# triacTriggerCpuBoard.net
KiCad netlist of a schematic drawn in EAGLE
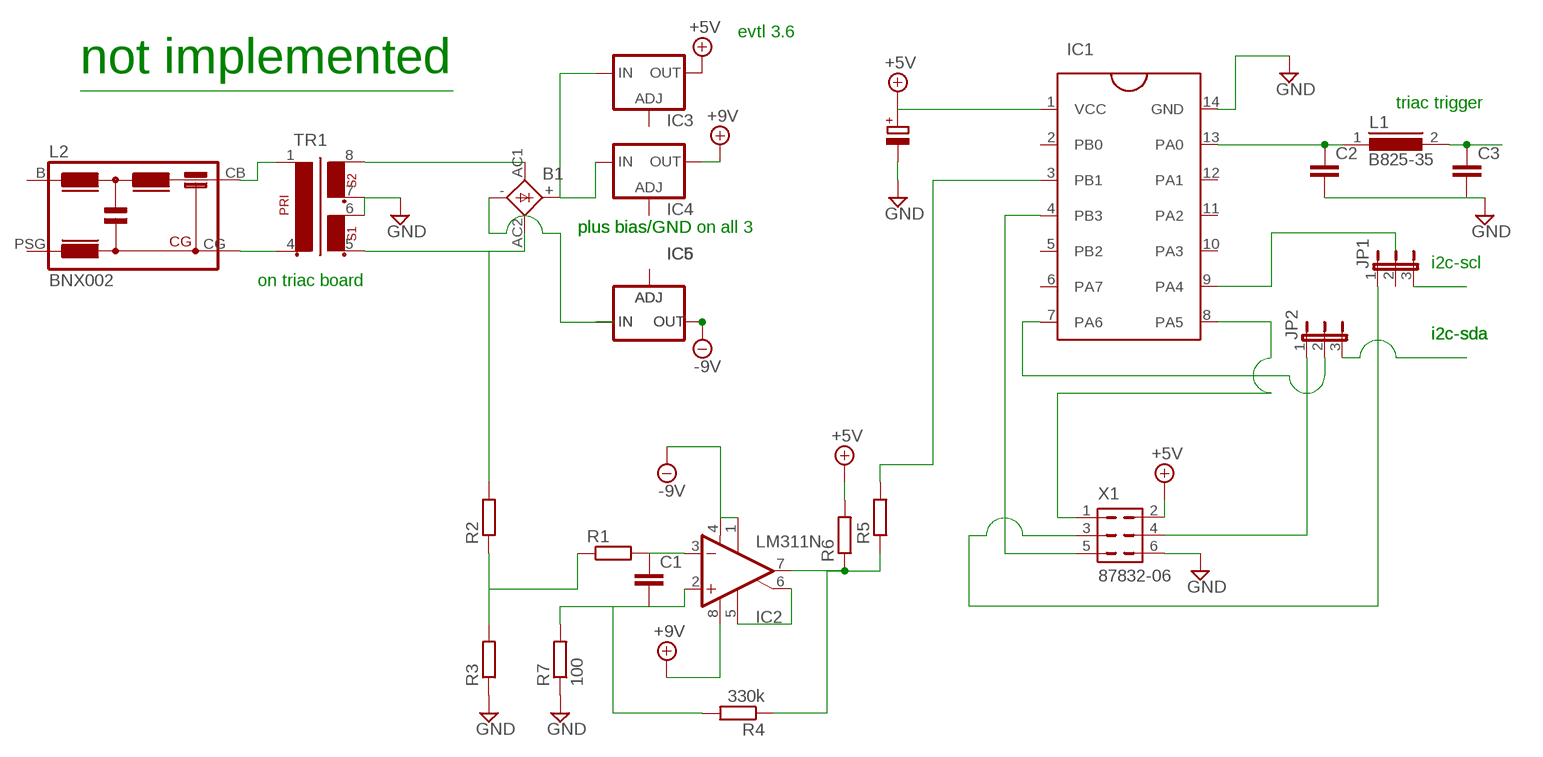
[diagram p0: schematic, sheet 1]

(export (version "E")
  (design (tool "Eeschema 10.0.6"))
  (components
    (comp (ref "B1")
      (value "2KBB-R")
      (footprint "eagle-import:2KBB-R")
      (libsource (lib "eagle-import") (part "2KBB-R"))
    )
    (comp (ref "C1")
      (value "C2,5-3")
      (footprint "eagle-import:C2.5-3")
      (libsource (lib "eagle-import") (part "C2,5-3"))
    )
    (comp (ref "C2")
      (value "C2,5-3")
      (footprint "eagle-import:C2.5-3")
      (libsource (lib "eagle-import") (part "C2,5-3"))
    )
    (comp (ref "C3")
      (value "C2,5-3")
      (footprint "eagle-import:C2.5-3")
      (libsource (lib "eagle-import") (part "C2,5-3"))
    )
    (comp (ref "IC1")
      (value "ATTINY4414P3")
      (footprint "eagle-import:DIL14")
      (libsource (lib "eagle-import") (part "ATTINY4414P3"))
    )
    (comp (ref "IC2")
      (value "LM311N")
      (footprint "eagle-import:DIL08")
      (libsource (lib "eagle-import") (part "LM311N"))
    )
    (comp (ref "IC3")
      (value "LM317-TO3")
      (footprint "eagle-import:TO3-K02")
      (libsource (lib "eagle-import") (part "LM317-TO3"))
    )
    (comp (ref "IC4")
      (value "LM317-TO3")
      (footprint "eagle-import:TO3-K02")
      (libsource (lib "eagle-import") (part "LM317-TO3"))
    )
    (comp (ref "IC5")
      (value "LM337TS")
      (footprint "eagle-import:337TS")
      (libsource (lib "eagle-import") (part "LM337TS"))
    )
    (comp (ref "IC6")
      (value "LM337TS")
      (footprint "eagle-import:337TS")
      (libsource (lib "eagle-import") (part "LM337TS"))
    )
    (comp (ref "JP1")
      (value "JP2E")
      (footprint "eagle-import:JP2")
      (libsource (lib "eagle-import") (part "JP2E"))
    )
    (comp (ref "JP2")
      (value "JP2E")
      (footprint "eagle-import:JP2")
      (libsource (lib "eagle-import") (part "JP2E"))
    )
    (comp (ref "L1")
      (value "B825-35")
      (footprint "eagle-import:B825-35")
      (libsource (lib "eagle-import") (part "B825-35"))
    )
    (comp (ref "L2")
      (value "BNX002")
      (footprint "eagle-import:BNX002")
      (libsource (lib "eagle-import") (part "BNX002"))
    )
    (comp (ref "R1")
      (value "R-EU_0207/10")
      (footprint "eagle-import:0207_10")
      (libsource (lib "eagle-import") (part "R-EU_0207/10"))
    )
    (comp (ref "R2")
      (value "R-EU_0207/10")
      (footprint "eagle-import:0207_10")
      (libsource (lib "eagle-import") (part "R-EU_0207/10"))
    )
    (comp (ref "R3")
      (value "R-EU_0207/10")
      (footprint "eagle-import:0207_10")
      (libsource (lib "eagle-import") (part "R-EU_0207/10"))
    )
    (comp (ref "R4")
      (value "330k")
      (footprint "eagle-import:0207_10")
      (libsource (lib "eagle-import") (part "R-EU_0207/10"))
    )
    (comp (ref "R5")
      (value "R-EU_0207/10")
      (footprint "eagle-import:0207_10")
      (libsource (lib "eagle-import") (part "R-EU_0207/10"))
    )
    (comp (ref "R6")
      (value "R-EU_0207/10")
      (footprint "eagle-import:0207_10")
      (libsource (lib "eagle-import") (part "R-EU_0207/10"))
    )
    (comp (ref "R7")
      (value "100")
      (footprint "eagle-import:0207_10")
      (libsource (lib "eagle-import") (part "R-EU_0207/10"))
    )
    (comp (ref "TR1")
      (value "EE20-2")
      (footprint "eagle-import:EE20-2")
      (libsource (lib "eagle-import") (part "EE20-2"))
    )
    (comp (ref "X1")
      (value "87832-06")
      (footprint "eagle-import:87832-06")
      (libsource (lib "eagle-import") (part "87832-06"))
    )
  )
  (nets
    (net (code "1") (name "+5V") (class "Default")
      (node (ref "IC1") (pin "1") (pinfunction "VCC_1") (pintype "power_in"))
      (node (ref "IC3") (pin "3") (pinfunction "OUT_3") (pintype "passive"))
      (node (ref "R6") (pin "2") (pinfunction "2_2") (pintype "passive"))
      (node (ref "X1") (pin "2") (pinfunction "2_2") (pintype "passive"))
    )
    (net (code "2") (name "+9V") (class "Default")
      (node (ref "IC2") (pin "8") (pinfunction "V+_8") (pintype "power_in"))
      (node (ref "IC4") (pin "3") (pinfunction "OUT_3") (pintype "passive"))
    )
    (net (code "3") (name "-9V") (class "Default")
      (node (ref "IC2") (pin "1") (pinfunction "GND_1") (pintype "passive"))
      (node (ref "IC2") (pin "4") (pinfunction "V-_4") (pintype "power_in"))
      (node (ref "IC5") (pin "3") (pinfunction "OUT_3") (pintype "passive"))
      (node (ref "IC6") (pin "3") (pinfunction "OUT_3") (pintype "passive"))
    )
    (net (code "4") (name "GND") (class "Default")
      (node (ref "C2") (pin "2") (pinfunction "2_2") (pintype "passive"))
      (node (ref "IC1") (pin "14") (pinfunction "GND_14") (pintype "power_in"))
      (node (ref "R3") (pin "1") (pinfunction "1_1") (pintype "passive"))
      (node (ref "R7") (pin "1") (pinfunction "1_1") (pintype "passive"))
      (node (ref "TR1") (pin "6") (pinfunction "4_6") (pintype "passive"))
      (node (ref "TR1") (pin "7") (pinfunction "5_7") (pintype "passive"))
      (node (ref "X1") (pin "6") (pinfunction "6_6") (pintype "passive"))
    )
    (net (code "5") (name "Net-(C3-Pad1)") (class "Default")
      (node (ref "C3") (pin "1") (pinfunction "1_1") (pintype "passive"))
      (node (ref "L1") (pin "2") (pinfunction "2_2") (pintype "passive"))
    )
    (net (code "6") (name "Net-(IC1-PA0)") (class "Default")
      (node (ref "C2") (pin "1") (pinfunction "1_1") (pintype "passive"))
      (node (ref "IC1") (pin "13") (pinfunction "PA0_13") (pintype "bidirectional"))
      (node (ref "L1") (pin "1") (pinfunction "1_1") (pintype "passive"))
    )
    (net (code "7") (name "Net-(IC1-PA5)") (class "Default")
      (node (ref "IC1") (pin "8") (pinfunction "PA5_8") (pintype "bidirectional"))
      (node (ref "X1") (pin "1") (pinfunction "1_1") (pintype "passive"))
    )
    (net (code "8") (name "Net-(IC1-PA6)") (class "Default")
      (node (ref "IC1") (pin "7") (pinfunction "PA6_7") (pintype "bidirectional"))
      (node (ref "JP2") (pin "2") (pinfunction "2_2") (pintype "passive"))
    )
    (net (code "9") (name "Net-(IC1-PB1)") (class "Default")
      (node (ref "IC1") (pin "3") (pinfunction "PB1_3") (pintype "bidirectional"))
      (node (ref "R5") (pin "2") (pinfunction "2_2") (pintype "passive"))
    )
    (net (code "10") (name "Net-(IC1-PB3)") (class "Default")
      (node (ref "IC1") (pin "4") (pinfunction "PB3_4") (pintype "bidirectional"))
      (node (ref "X1") (pin "5") (pinfunction "5_5") (pintype "passive"))
    )
    (net (code "11") (name "Net-(IC2-+IN)") (class "Default")
      (node (ref "C1") (pin "2") (pinfunction "2_2") (pintype "passive"))
      (node (ref "IC2") (pin "2") (pinfunction "+IN_2") (pintype "input"))
      (node (ref "R4") (pin "2") (pinfunction "2_2") (pintype "passive"))
      (node (ref "R7") (pin "2") (pinfunction "2_2") (pintype "passive"))
    )
    (net (code "12") (name "Net-(IC2--IN)") (class "Default")
      (node (ref "C1") (pin "1") (pinfunction "1_1") (pintype "passive"))
      (node (ref "IC2") (pin "3") (pinfunction "-IN_3") (pintype "input"))
      (node (ref "R1") (pin "2") (pinfunction "2_2") (pintype "passive"))
    )
    (net (code "13") (name "Net-(IC2-ON)") (class "Default")
      (node (ref "IC2") (pin "5") (pinfunction "ON_5") (pintype "passive"))
      (node (ref "IC2") (pin "6") (pinfunction "ON/STR_6") (pintype "passive"))
    )
    (net (code "14") (name "Net-(IC2-OUT)") (class "Default")
      (node (ref "IC2") (pin "7") (pinfunction "OUT_7") (pintype "output"))
      (node (ref "R4") (pin "1") (pinfunction "1_1") (pintype "passive"))
      (node (ref "R5") (pin "1") (pinfunction "1_1") (pintype "passive"))
      (node (ref "R6") (pin "1") (pinfunction "1_1") (pintype "passive"))
    )
    (net (code "15") (name "Net-(IC3-IN)") (class "Default")
      (node (ref "B1") (pin "+") (pinfunction "+_+") (pintype "passive"))
      (node (ref "IC3") (pin "1") (pinfunction "IN_1") (pintype "input"))
      (node (ref "IC4") (pin "1") (pinfunction "IN_1") (pintype "input"))
    )
    (net (code "16") (name "Net-(IC5-ADJ)") (class "Default")
      (node (ref "IC5") (pin "1") (pinfunction "ADJ_1") (pintype "input"))
      (node (ref "IC6") (pin "1") (pinfunction "ADJ_1") (pintype "input"))
    )
    (net (code "17") (name "Net-(IC5-IN)") (class "Default")
      (node (ref "B1") (pin "-") (pinfunction "-_-") (pintype "passive"))
      (node (ref "IC5") (pin "2") (pinfunction "IN_2") (pintype "input"))
      (node (ref "IC6") (pin "2") (pinfunction "IN_2") (pintype "input"))
    )
    (net (code "18") (name "Net-(JP1-Pad1)") (class "Default")
      (node (ref "JP1") (pin "1") (pinfunction "1_1") (pintype "passive"))
      (node (ref "X1") (pin "3") (pinfunction "3_3") (pintype "passive"))
    )
    (net (code "19") (name "Net-(JP2-Pad1)") (class "Default")
      (node (ref "JP2") (pin "1") (pinfunction "1_1") (pintype "passive"))
      (node (ref "X1") (pin "4") (pinfunction "4_4") (pintype "passive"))
    )
    (net (code "20") (name "Net-(L2-PadCB)") (class "Default")
      (node (ref "L2") (pin "CB") (pinfunction "CB_CB") (pintype "passive"))
      (node (ref "TR1") (pin "1") (pinfunction "1_1") (pintype "passive"))
    )
    (net (code "21") (name "Net-(R1-Pad1)") (class "Default")
      (node (ref "R1") (pin "1") (pinfunction "1_1") (pintype "passive"))
      (node (ref "R2") (pin "1") (pinfunction "1_1") (pintype "passive"))
      (node (ref "R3") (pin "2") (pinfunction "2_2") (pintype "passive"))
    )
    (net (code "22") (name "Net-(TR1-2)") (class "Default")
      (node (ref "L2") (pin "CG") (pinfunction "CG_CG") (pintype "passive"))
      (node (ref "TR1") (pin "4") (pinfunction "2_4") (pintype "passive"))
    )
    (net (code "23") (name "Net-(TR1-3)") (class "Default")
      (node (ref "B1") (pin "AC2") (pinfunction "AC2_AC2") (pintype "passive"))
      (node (ref "R2") (pin "2") (pinfunction "2_2") (pintype "passive"))
      (node (ref "TR1") (pin "5") (pinfunction "3_5") (pintype "passive"))
    )
    (net (code "24") (name "Net-(TR1-6)") (class "Default")
      (node (ref "B1") (pin "AC1") (pinfunction "AC1_AC1") (pintype "passive"))
      (node (ref "TR1") (pin "8") (pinfunction "6_8") (pintype "passive"))
    )
    (net (code "25") (name "unconnected-(C3-Pad2)") (class "Default")
      (node (ref "C3") (pin "2") (pinfunction "2_2") (pintype "passive"))
    )
    (net (code "26") (name "unconnected-(IC1-PA1-Pad12)") (class "Default")
      (node (ref "IC1") (pin "12") (pinfunction "PA1_12") (pintype "bidirectional"))
    )
    (net (code "27") (name "unconnected-(IC1-PA2-Pad11)") (class "Default")
      (node (ref "IC1") (pin "11") (pinfunction "PA2_11") (pintype "bidirectional"))
    )
    (net (code "28") (name "unconnected-(IC1-PA3-Pad10)") (class "Default")
      (node (ref "IC1") (pin "10") (pinfunction "PA3_10") (pintype "bidirectional"))
    )
    (net (code "29") (name "unconnected-(IC1-PA4-Pad9)") (class "Default")
      (node (ref "IC1") (pin "9") (pinfunction "PA4_9") (pintype "bidirectional"))
    )
    (net (code "30") (name "unconnected-(IC1-PA7-Pad6)") (class "Default")
      (node (ref "IC1") (pin "6") (pinfunction "PA7_6") (pintype "bidirectional"))
    )
    (net (code "31") (name "unconnected-(IC1-PB0-Pad2)") (class "Default")
      (node (ref "IC1") (pin "2") (pinfunction "PB0_2") (pintype "bidirectional"))
    )
    (net (code "32") (name "unconnected-(IC1-PB2-Pad5)") (class "Default")
      (node (ref "IC1") (pin "5") (pinfunction "PB2_5") (pintype "bidirectional"))
    )
    (net (code "33") (name "unconnected-(IC3-ADJ-Pad2)") (class "Default")
      (node (ref "IC3") (pin "2") (pinfunction "ADJ_2") (pintype "input"))
    )
    (net (code "34") (name "unconnected-(IC4-ADJ-Pad2)") (class "Default")
      (node (ref "IC4") (pin "2") (pinfunction "ADJ_2") (pintype "input"))
    )
    (net (code "35") (name "unconnected-(JP1-Pad2)") (class "Default")
      (node (ref "JP1") (pin "2") (pinfunction "2_2") (pintype "passive"))
    )
    (net (code "36") (name "unconnected-(JP1-Pad3)") (class "Default")
      (node (ref "JP1") (pin "3") (pinfunction "3_3") (pintype "passive"))
    )
    (net (code "37") (name "unconnected-(JP2-Pad3)") (class "Default")
      (node (ref "JP2") (pin "3") (pinfunction "3_3") (pintype "passive"))
    )
    (net (code "38") (name "unconnected-(L2-PadB)") (class "Default")
      (node (ref "L2") (pin "B") (pinfunction "B_B") (pintype "passive"))
    )
    (net (code "39") (name "unconnected-(L2-PadPSG)") (class "Default")
      (node (ref "L2") (pin "PSG") (pinfunction "PSG_PSG") (pintype "passive"))
    )
  )
)
